# network_board_header.net
KiCad netlist of a schematic drawn in EAGLE
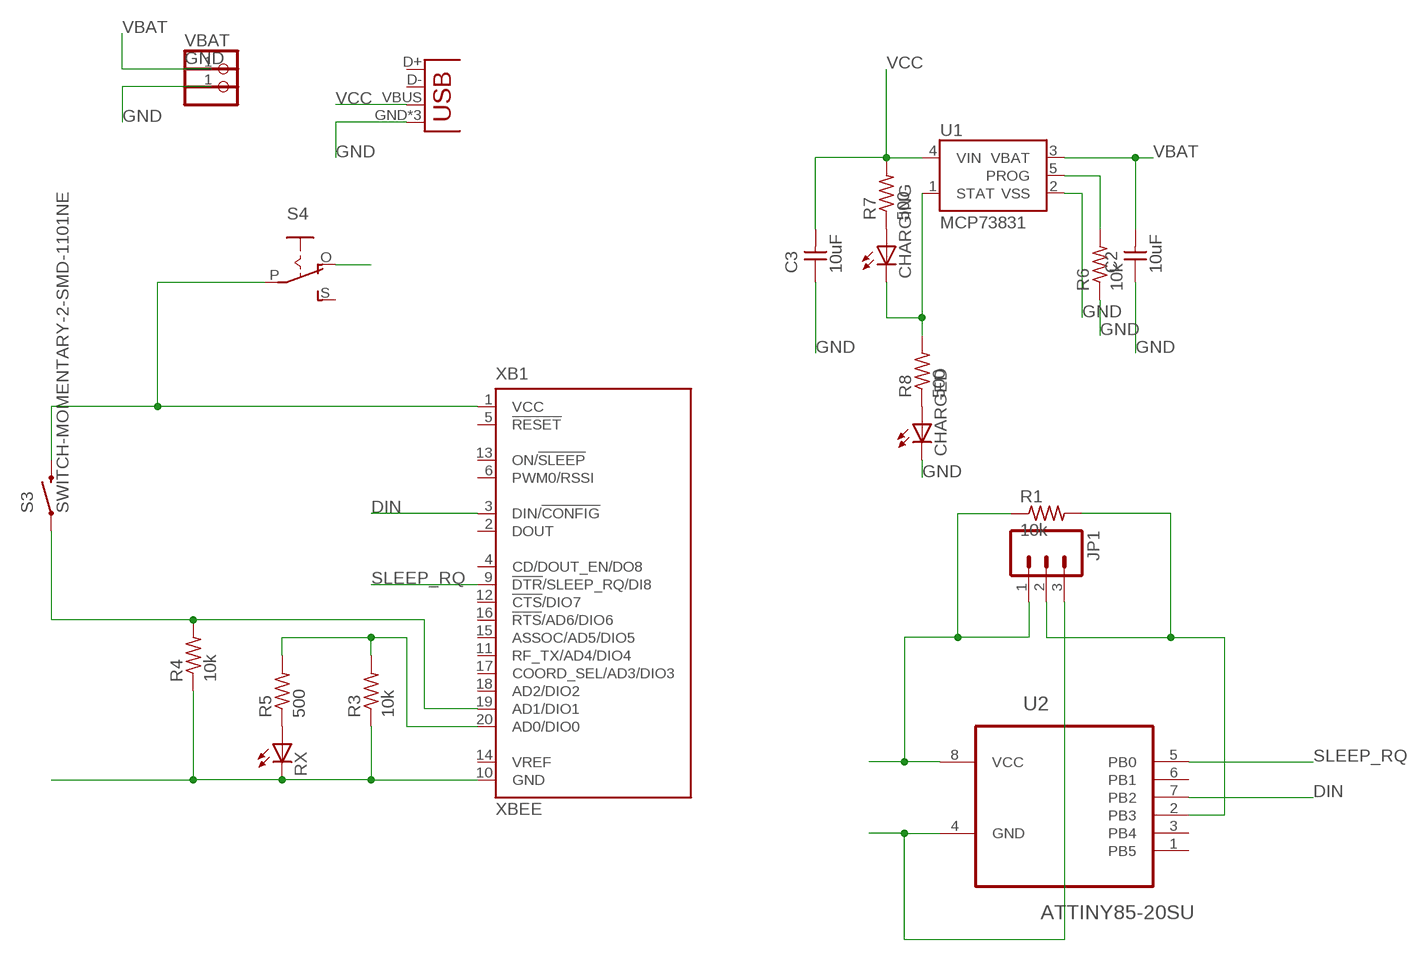
[diagram p0: schematic, sheet 1]

(export (version "E")
  (design (tool "Eeschema 10.0.6"))
  (components
    (comp (ref "C2")
      (value "10uF")
      (footprint "eagle-import:1206")
      (libsource (lib "eagle-import") (part "UNPOLARIZED_CAPACITOR1206"))
    )
    (comp (ref "C3")
      (value "10uF")
      (footprint "eagle-import:1206")
      (libsource (lib "eagle-import") (part "UNPOLARIZED_CAPACITOR1206"))
    )
    (comp (ref "CHARGED")
      (value "LED1206")
      (footprint "eagle-import:1206")
      (libsource (lib "eagle-import") (part "LED1206"))
    )
    (comp (ref "CHARGING")
      (value "LED1206")
      (footprint "eagle-import:1206")
      (libsource (lib "eagle-import") (part "LED1206"))
    )
    (comp (ref "GND")
      (value "PINHD-1X1CB")
      (footprint "eagle-import:1X01-CLEANBIG")
      (libsource (lib "eagle-import") (part "PINHD-1X1CB"))
    )
    (comp (ref "JP1")
      (value "M03PTH")
      (footprint "eagle-import:1X03")
      (libsource (lib "eagle-import") (part "M03PTH"))
    )
    (comp (ref "R1")
      (value "10k")
      (footprint "eagle-import:1206")
      (libsource (lib "eagle-import") (part "RESISTOR1206"))
    )
    (comp (ref "R3")
      (value "10k")
      (footprint "eagle-import:R1206")
      (libsource (lib "eagle-import") (part "RES-US1206"))
    )
    (comp (ref "R4")
      (value "10k")
      (footprint "eagle-import:R1206")
      (libsource (lib "eagle-import") (part "RES-US1206"))
    )
    (comp (ref "R5")
      (value "500")
      (footprint "eagle-import:R1206")
      (libsource (lib "eagle-import") (part "RES-US1206"))
    )
    (comp (ref "R6")
      (value "10k")
      (footprint "eagle-import:R1206")
      (libsource (lib "eagle-import") (part "RES-US1206"))
    )
    (comp (ref "R7")
      (value "500")
      (footprint "eagle-import:R1206")
      (libsource (lib "eagle-import") (part "RES-US1206"))
    )
    (comp (ref "R8")
      (value "500")
      (footprint "eagle-import:R1206")
      (libsource (lib "eagle-import") (part "RES-US1206"))
    )
    (comp (ref "RX")
      (value "LED1206")
      (footprint "eagle-import:1206")
      (libsource (lib "eagle-import") (part "LED1206"))
    )
    (comp (ref "S3")
      (value "SWITCH-MOMENTARY-2-SMD-1101NE")
      (footprint "eagle-import:TACTILE-SWITCH-1101NE")
      (libsource (lib "eagle-import") (part "SWITCH-MOMENTARY-2-SMD-1101NE"))
    )
    (comp (ref "S4")
      (value "EG1218S")
      (footprint "eagle-import:EG1218")
      (libsource (lib "eagle-import") (part "EG1218S"))
    )
    (comp (ref "U1")
      (value "MCP73831")
      (footprint "eagle-import:SOT23-5")
      (libsource (lib "eagle-import") (part "MCP73831"))
    )
    (comp (ref "U2")
      (value "ATTINY85-20SU")
      (footprint "eagle-import:SOIC127P798X216-8N")
      (libsource (lib "eagle-import") (part "ATTINY85-20SU"))
    )
    (comp (ref "VBAT")
      (value "PINHD-1X1CB")
      (footprint "eagle-import:1X01-CLEANBIG")
      (libsource (lib "eagle-import") (part "PINHD-1X1CB"))
    )
    (comp (ref "X1")
      (value "USB-MICROB")
      (footprint "eagle-import:USB-MICROB")
      (libsource (lib "eagle-import") (part "USB-MICROB"))
    )
    (comp (ref "XB1")
      (value "XBEE")
      (footprint "eagle-import:XBEE")
      (fields (field (name "MPN") "XBP24-Z7UIT-004"))
      (libsource (lib "eagle-import") (part "XBEE"))
    )
  )
  (nets
    (net (code "1") (name "/DIN") (class "Default")
      (node (ref "U2") (pin "7") (pinfunction "PB2_7") (pintype "bidirectional"))
      (node (ref "XB1") (pin "3") (pinfunction "DIN/~{CONFIG}_3") (pintype "input"))
    )
    (net (code "2") (name "/GND") (class "Default")
      (node (ref "C2") (pin "1") (pinfunction "1_1") (pintype "passive"))
      (node (ref "C3") (pin "1") (pinfunction "1_1") (pintype "passive"))
      (node (ref "CHARGED") (pin "2") (pinfunction "C_2") (pintype "passive"))
      (node (ref "GND") (pin "1") (pinfunction "1_1") (pintype "passive"))
      (node (ref "JP1") (pin "3") (pinfunction "3_3") (pintype "passive"))
      (node (ref "R3") (pin "1") (pinfunction "1_1") (pintype "passive"))
      (node (ref "R4") (pin "1") (pinfunction "1_1") (pintype "passive"))
      (node (ref "R6") (pin "1") (pinfunction "1_1") (pintype "passive"))
      (node (ref "RX") (pin "2") (pinfunction "C_2") (pintype "passive"))
      (node (ref "U1") (pin "2") (pinfunction "VSS_2") (pintype "power_in"))
      (node (ref "U2") (pin "4") (pinfunction "GND_4") (pintype "passive"))
      (node (ref "X1") (pin "GND") (pinfunction "GND_GND") (pintype "bidirectional"))
      (node (ref "X1") (pin "MT1") (pinfunction "GND_MT1") (pintype "bidirectional"))
      (node (ref "X1") (pin "MT2") (pinfunction "GND_MT2") (pintype "bidirectional"))
      (node (ref "XB1") (pin "10") (pinfunction "GND_10") (pintype "power_in"))
    )
    (net (code "3") (name "/SLEEP_RQ") (class "Default")
      (node (ref "U2") (pin "5") (pinfunction "PB0_5") (pintype "bidirectional"))
      (node (ref "XB1") (pin "9") (pinfunction "~{DTR}/SLEEP_RQ/DI8_9") (pintype "bidirectional"))
    )
    (net (code "4") (name "/VBAT") (class "Default")
      (node (ref "C2") (pin "2") (pinfunction "2_2") (pintype "passive"))
      (node (ref "S4") (pin "O") (pinfunction "O_O") (pintype "passive"))
      (node (ref "U1") (pin "3") (pinfunction "VBAT_3") (pintype "power_in"))
      (node (ref "VBAT") (pin "1") (pinfunction "1_1") (pintype "passive"))
    )
    (net (code "5") (name "/VCC") (class "Default")
      (node (ref "C3") (pin "2") (pinfunction "2_2") (pintype "passive"))
      (node (ref "R7") (pin "2") (pinfunction "2_2") (pintype "passive"))
      (node (ref "U1") (pin "4") (pinfunction "VIN_4") (pintype "power_in"))
      (node (ref "X1") (pin "VBUS") (pinfunction "VBUS_VBUS") (pintype "bidirectional"))
    )
    (net (code "6") (name "/VIN") (class "Default")
      (node (ref "JP1") (pin "1") (pinfunction "1_1") (pintype "passive"))
      (node (ref "R1") (pin "1") (pinfunction "1_1") (pintype "passive"))
      (node (ref "S3") (pin "P$2") (pinfunction "2_P$2") (pintype "passive"))
      (node (ref "S4") (pin "P") (pinfunction "P_P") (pintype "passive"))
      (node (ref "U2") (pin "8") (pinfunction "VCC_8") (pintype "power_in"))
      (node (ref "XB1") (pin "1") (pinfunction "VCC_1") (pintype "power_in"))
    )
    (net (code "7") (name "Net-(CHARGED-A)") (class "Default")
      (node (ref "CHARGED") (pin "1") (pinfunction "A_1") (pintype "passive"))
      (node (ref "R8") (pin "1") (pinfunction "1_1") (pintype "passive"))
    )
    (net (code "8") (name "Net-(CHARGING-A)") (class "Default")
      (node (ref "CHARGING") (pin "1") (pinfunction "A_1") (pintype "passive"))
      (node (ref "R7") (pin "1") (pinfunction "1_1") (pintype "passive"))
    )
    (net (code "9") (name "Net-(CHARGING-C)") (class "Default")
      (node (ref "CHARGING") (pin "2") (pinfunction "C_2") (pintype "passive"))
      (node (ref "R8") (pin "2") (pinfunction "2_2") (pintype "passive"))
      (node (ref "U1") (pin "1") (pinfunction "STAT_1") (pintype "output"))
    )
    (net (code "10") (name "Net-(RX-A)") (class "Default")
      (node (ref "R5") (pin "1") (pinfunction "1_1") (pintype "passive"))
      (node (ref "RX") (pin "1") (pinfunction "A_1") (pintype "passive"))
    )
    (net (code "11") (name "Net-(S3-1)") (class "Default")
      (node (ref "R4") (pin "2") (pinfunction "2_2") (pintype "passive"))
      (node (ref "S3") (pin "P$1") (pinfunction "1_P$1") (pintype "passive"))
      (node (ref "XB1") (pin "19") (pinfunction "AD1/DIO1_19") (pintype "bidirectional"))
    )
    (net (code "12") (name "Net-(U1-PROG)") (class "Default")
      (node (ref "R6") (pin "2") (pinfunction "2_2") (pintype "passive"))
      (node (ref "U1") (pin "5") (pinfunction "PROG_5") (pintype "input"))
    )
    (net (code "13") (name "Net-(U2-PB3)") (class "Default")
      (node (ref "JP1") (pin "2") (pinfunction "2_2") (pintype "passive"))
      (node (ref "R1") (pin "2") (pinfunction "2_2") (pintype "passive"))
      (node (ref "U2") (pin "2") (pinfunction "PB3_2") (pintype "bidirectional"))
    )
    (net (code "14") (name "Net-(XB1-AD0{slash}DIO0)") (class "Default")
      (node (ref "R3") (pin "2") (pinfunction "2_2") (pintype "passive"))
      (node (ref "R5") (pin "2") (pinfunction "2_2") (pintype "passive"))
      (node (ref "XB1") (pin "20") (pinfunction "AD0/DIO0_20") (pintype "bidirectional"))
    )
    (net (code "15") (name "unconnected-(S4-PadS)") (class "Default")
      (node (ref "S4") (pin "S") (pinfunction "S_S") (pintype "passive"))
    )
    (net (code "16") (name "unconnected-(U2-PB1-Pad6)") (class "Default")
      (node (ref "U2") (pin "6") (pinfunction "PB1_6") (pintype "bidirectional"))
    )
    (net (code "17") (name "unconnected-(U2-PB4-Pad3)") (class "Default")
      (node (ref "U2") (pin "3") (pinfunction "PB4_3") (pintype "bidirectional"))
    )
    (net (code "18") (name "unconnected-(U2-PB5-Pad1)") (class "Default")
      (node (ref "U2") (pin "1") (pinfunction "PB5_1") (pintype "bidirectional"))
    )
    (net (code "19") (name "unconnected-(X1-PadD+)") (class "Default")
      (node (ref "X1") (pin "D+") (pinfunction "D+_D+") (pintype "bidirectional"))
    )
    (net (code "20") (name "unconnected-(X1-PadD-)") (class "Default")
      (node (ref "X1") (pin "D-") (pinfunction "D-_D-") (pintype "bidirectional"))
    )
    (net (code "21") (name "unconnected-(XB1-AD2{slash}DIO2-Pad18)") (class "Default")
      (node (ref "XB1") (pin "18") (pinfunction "AD2/DIO2_18") (pintype "bidirectional"))
    )
    (net (code "22") (name "unconnected-(XB1-ASSOC{slash}AD5{slash}DIO5-Pad15)") (class "Default")
      (node (ref "XB1") (pin "15") (pinfunction "ASSOC/AD5/DIO5_15") (pintype "bidirectional"))
    )
    (net (code "23") (name "unconnected-(XB1-CD{slash}DOUT_EN{slash}DO8-Pad4)") (class "Default")
      (node (ref "XB1") (pin "4") (pinfunction "CD/DOUT_EN/DO8_4") (pintype "output"))
    )
    (net (code "24") (name "unconnected-(XB1-COORD_SEL{slash}AD3{slash}DIO3-Pad17)") (class "Default")
      (node (ref "XB1") (pin "17") (pinfunction "COORD_SEL/AD3/DIO3_17") (pintype "bidirectional"))
    )
    (net (code "25") (name "unconnected-(XB1-DOUT-Pad2)") (class "Default")
      (node (ref "XB1") (pin "2") (pinfunction "DOUT_2") (pintype "output"))
    )
    (net (code "26") (name "unconnected-(XB1-ON{slash}~{SLEEP}-Pad13)") (class "Default")
      (node (ref "XB1") (pin "13") (pinfunction "ON/~{SLEEP}_13") (pintype "output"))
    )
    (net (code "27") (name "unconnected-(XB1-PWM0{slash}RSSI-Pad6)") (class "Default")
      (node (ref "XB1") (pin "6") (pinfunction "PWM0/RSSI_6") (pintype "output"))
    )
    (net (code "28") (name "unconnected-(XB1-RF_TX{slash}AD4{slash}DIO4-Pad11)") (class "Default")
      (node (ref "XB1") (pin "11") (pinfunction "RF_TX/AD4/DIO4_11") (pintype "bidirectional"))
    )
    (net (code "29") (name "unconnected-(XB1-VREF-Pad14)") (class "Default")
      (node (ref "XB1") (pin "14") (pinfunction "VREF_14") (pintype "input"))
    )
    (net (code "30") (name "unconnected-(XB1-~{CTS}{slash}DIO7-Pad12)") (class "Default")
      (node (ref "XB1") (pin "12") (pinfunction "~{CTS}/DIO7_12") (pintype "bidirectional"))
    )
    (net (code "31") (name "unconnected-(XB1-~{RESET}-Pad5)") (class "Default")
      (node (ref "XB1") (pin "5") (pinfunction "~{RESET}_5") (pintype "input"))
    )
    (net (code "32") (name "unconnected-(XB1-~{RTS}{slash}AD6{slash}DIO6-Pad16)") (class "Default")
      (node (ref "XB1") (pin "16") (pinfunction "~{RTS}/AD6/DIO6_16") (pintype "bidirectional"))
    )
  )
)
